# ManualShield.net
KiCad netlist of a schematic drawn in EAGLE
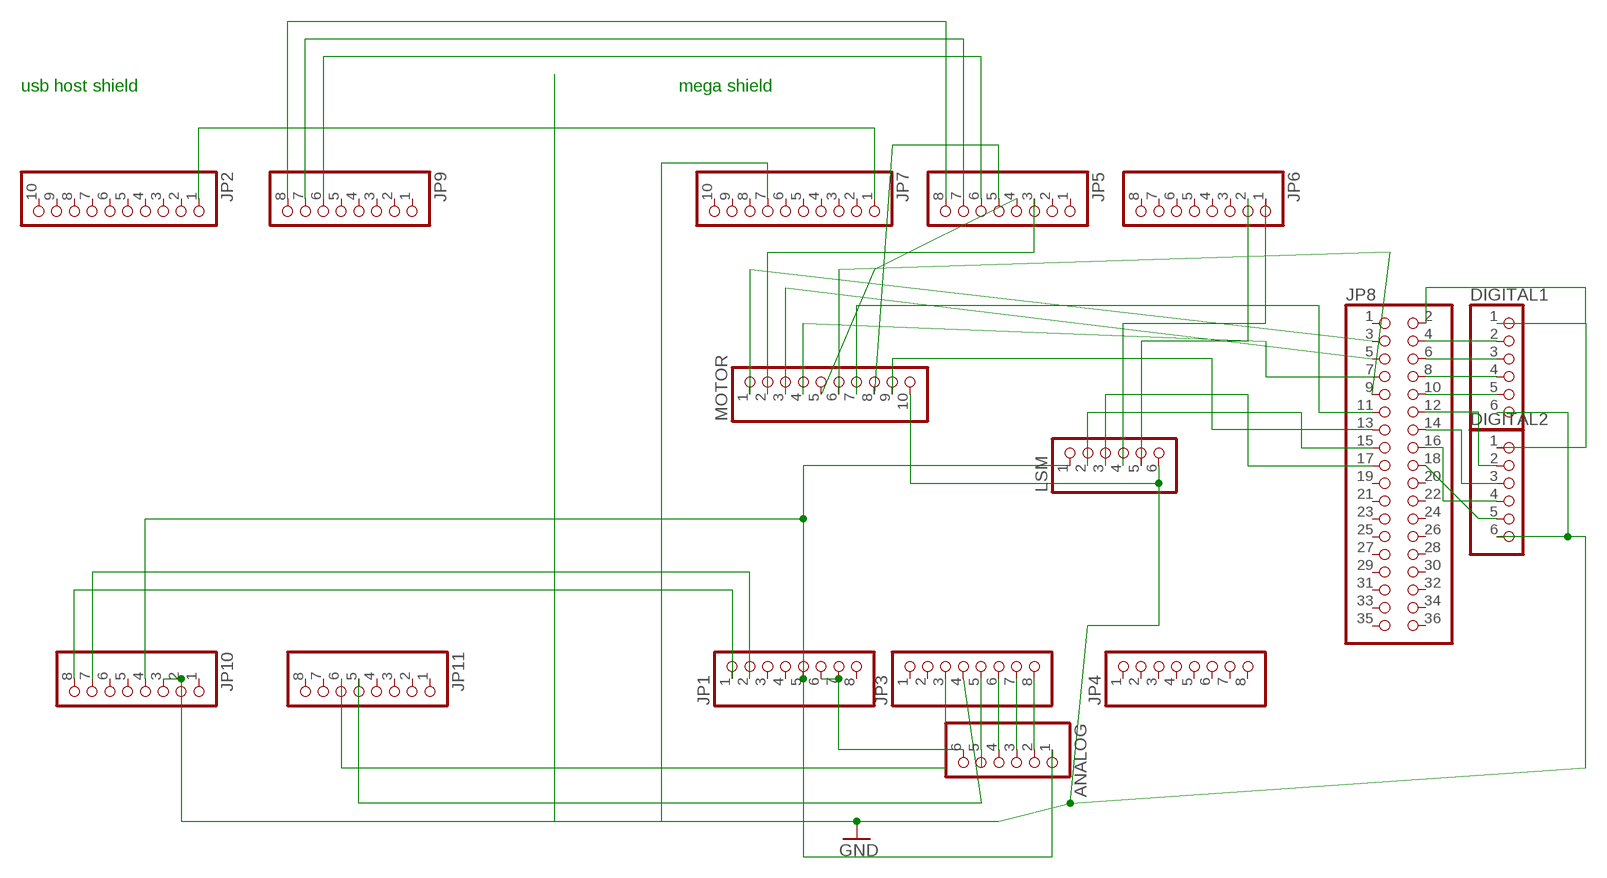
[diagram p0: schematic, sheet 1]

(export (version "E")
  (design (tool "Eeschema 10.0.6"))
  (components
    (comp (ref "ANALOG")
      (value "PINHD-1X6")
      (footprint "eagle-import:1X06")
      (libsource (lib "eagle-import") (part "PINHD-1X6"))
    )
    (comp (ref "DIGITAL1")
      (value "PINHD-1X6")
      (footprint "eagle-import:1X06")
      (libsource (lib "eagle-import") (part "PINHD-1X6"))
    )
    (comp (ref "DIGITAL2")
      (value "PINHD-1X6")
      (footprint "eagle-import:1X06")
      (libsource (lib "eagle-import") (part "PINHD-1X6"))
    )
    (comp (ref "JP1")
      (value "PINHD-1X8")
      (footprint "eagle-import:1X08")
      (libsource (lib "eagle-import") (part "PINHD-1X8"))
    )
    (comp (ref "JP2")
      (value "PINHD-1X10")
      (footprint "eagle-import:1X10")
      (libsource (lib "eagle-import") (part "PINHD-1X10"))
    )
    (comp (ref "JP3")
      (value "PINHD-1X8")
      (footprint "eagle-import:1X08")
      (libsource (lib "eagle-import") (part "PINHD-1X8"))
    )
    (comp (ref "JP4")
      (value "PINHD-1X8")
      (footprint "eagle-import:1X08")
      (libsource (lib "eagle-import") (part "PINHD-1X8"))
    )
    (comp (ref "JP5")
      (value "PINHD-1X8")
      (footprint "eagle-import:1X08")
      (libsource (lib "eagle-import") (part "PINHD-1X8"))
    )
    (comp (ref "JP6")
      (value "PINHD-1X8")
      (footprint "eagle-import:1X08")
      (libsource (lib "eagle-import") (part "PINHD-1X8"))
    )
    (comp (ref "JP7")
      (value "PINHD-1X10")
      (footprint "eagle-import:1X10")
      (libsource (lib "eagle-import") (part "PINHD-1X10"))
    )
    (comp (ref "JP8")
      (value "PINHD-2X18")
      (footprint "eagle-import:2X18")
      (libsource (lib "eagle-import") (part "PINHD-2X18"))
    )
    (comp (ref "JP9")
      (value "PINHD-1X8")
      (footprint "eagle-import:1X08")
      (libsource (lib "eagle-import") (part "PINHD-1X8"))
    )
    (comp (ref "JP10")
      (value "PINHD-1X8")
      (footprint "eagle-import:1X08")
      (libsource (lib "eagle-import") (part "PINHD-1X8"))
    )
    (comp (ref "JP11")
      (value "PINHD-1X8")
      (footprint "eagle-import:1X08")
      (libsource (lib "eagle-import") (part "PINHD-1X8"))
    )
    (comp (ref "LSM")
      (value "PINHD-1X6")
      (footprint "eagle-import:1X06")
      (libsource (lib "eagle-import") (part "PINHD-1X6"))
    )
    (comp (ref "MOTOR")
      (value "PINHD-1X10")
      (footprint "eagle-import:1X10")
      (libsource (lib "eagle-import") (part "pinhead_325_PINHD-1X10"))
    )
  )
  (nets
    (net (code "1") (name "GND") (class "Default")
      (node (ref "DIGITAL1") (pin "6") (pinfunction "6_6") (pintype "passive"))
      (node (ref "DIGITAL2") (pin "6") (pinfunction "6_6") (pintype "passive"))
      (node (ref "JP10") (pin "2") (pinfunction "2_2") (pintype "passive"))
      (node (ref "JP10") (pin "3") (pinfunction "3_3") (pintype "passive"))
      (node (ref "JP7") (pin "7") (pinfunction "7_7") (pintype "passive"))
      (node (ref "LSM") (pin "6") (pinfunction "6_6") (pintype "passive"))
      (node (ref "MOTOR") (pin "10") (pinfunction "10_10") (pintype "passive"))
    )
    (net (code "2") (name "Net-(ANALOG-Pad1)") (class "Default")
      (node (ref "ANALOG") (pin "1") (pinfunction "1_1") (pintype "passive"))
      (node (ref "JP1") (pin "5") (pinfunction "5_5") (pintype "passive"))
      (node (ref "JP10") (pin "4") (pinfunction "4_4") (pintype "passive"))
      (node (ref "LSM") (pin "1") (pinfunction "1_1") (pintype "passive"))
    )
    (net (code "3") (name "Net-(ANALOG-Pad2)") (class "Default")
      (node (ref "ANALOG") (pin "2") (pinfunction "2_2") (pintype "passive"))
      (node (ref "JP3") (pin "8") (pinfunction "8_8") (pintype "passive"))
    )
    (net (code "4") (name "Net-(ANALOG-Pad3)") (class "Default")
      (node (ref "ANALOG") (pin "3") (pinfunction "3_3") (pintype "passive"))
      (node (ref "JP3") (pin "7") (pinfunction "7_7") (pintype "passive"))
    )
    (net (code "5") (name "Net-(ANALOG-Pad4)") (class "Default")
      (node (ref "ANALOG") (pin "4") (pinfunction "4_4") (pintype "passive"))
      (node (ref "JP3") (pin "6") (pinfunction "6_6") (pintype "passive"))
    )
    (net (code "6") (name "Net-(ANALOG-Pad5)") (class "Default")
      (node (ref "ANALOG") (pin "5") (pinfunction "5_5") (pintype "passive"))
      (node (ref "JP3") (pin "5") (pinfunction "5_5") (pintype "passive"))
    )
    (net (code "7") (name "Net-(ANALOG-Pad6)") (class "Default")
      (node (ref "ANALOG") (pin "6") (pinfunction "6_6") (pintype "passive"))
      (node (ref "JP1") (pin "6") (pinfunction "6_6") (pintype "passive"))
      (node (ref "JP1") (pin "7") (pinfunction "7_7") (pintype "passive"))
    )
    (net (code "8") (name "Net-(DIGITAL1-Pad1)") (class "Default")
      (node (ref "DIGITAL1") (pin "1") (pinfunction "1_1") (pintype "passive"))
      (node (ref "DIGITAL2") (pin "1") (pinfunction "1_1") (pintype "passive"))
      (node (ref "JP8") (pin "2") (pinfunction "2_2") (pintype "passive"))
    )
    (net (code "9") (name "Net-(DIGITAL1-Pad2)") (class "Default")
      (node (ref "DIGITAL1") (pin "2") (pinfunction "2_2") (pintype "passive"))
      (node (ref "JP8") (pin "4") (pinfunction "4_4") (pintype "passive"))
    )
    (net (code "10") (name "Net-(DIGITAL1-Pad3)") (class "Default")
      (node (ref "DIGITAL1") (pin "3") (pinfunction "3_3") (pintype "passive"))
      (node (ref "JP8") (pin "6") (pinfunction "6_6") (pintype "passive"))
    )
    (net (code "11") (name "Net-(DIGITAL1-Pad4)") (class "Default")
      (node (ref "DIGITAL1") (pin "4") (pinfunction "4_4") (pintype "passive"))
      (node (ref "JP8") (pin "8") (pinfunction "8_8") (pintype "passive"))
    )
    (net (code "12") (name "Net-(DIGITAL1-Pad5)") (class "Default")
      (node (ref "DIGITAL1") (pin "5") (pinfunction "5_5") (pintype "passive"))
      (node (ref "JP8") (pin "10") (pinfunction "10_10") (pintype "passive"))
    )
    (net (code "13") (name "Net-(DIGITAL2-Pad2)") (class "Default")
      (node (ref "DIGITAL2") (pin "2") (pinfunction "2_2") (pintype "passive"))
      (node (ref "JP8") (pin "12") (pinfunction "12_12") (pintype "passive"))
    )
    (net (code "14") (name "Net-(DIGITAL2-Pad3)") (class "Default")
      (node (ref "DIGITAL2") (pin "3") (pinfunction "3_3") (pintype "passive"))
      (node (ref "JP8") (pin "14") (pinfunction "14_14") (pintype "passive"))
    )
    (net (code "15") (name "Net-(DIGITAL2-Pad4)") (class "Default")
      (node (ref "DIGITAL2") (pin "4") (pinfunction "4_4") (pintype "passive"))
      (node (ref "JP8") (pin "16") (pinfunction "16_16") (pintype "passive"))
    )
    (net (code "16") (name "Net-(DIGITAL2-Pad5)") (class "Default")
      (node (ref "DIGITAL2") (pin "5") (pinfunction "5_5") (pintype "passive"))
      (node (ref "JP8") (pin "18") (pinfunction "18_18") (pintype "passive"))
    )
    (net (code "17") (name "Net-(JP1-Pad1)") (class "Default")
      (node (ref "JP1") (pin "1") (pinfunction "1_1") (pintype "passive"))
      (node (ref "JP10") (pin "8") (pinfunction "8_8") (pintype "passive"))
    )
    (net (code "18") (name "Net-(JP1-Pad2)") (class "Default")
      (node (ref "JP1") (pin "2") (pinfunction "2_2") (pintype "passive"))
      (node (ref "JP10") (pin "7") (pinfunction "7_7") (pintype "passive"))
    )
    (net (code "19") (name "Net-(JP2-Pad1)") (class "Default")
      (node (ref "JP2") (pin "1") (pinfunction "1_1") (pintype "passive"))
      (node (ref "JP7") (pin "1") (pinfunction "1_1") (pintype "passive"))
    )
    (net (code "20") (name "Net-(JP5-Pad3)") (class "Default")
      (node (ref "JP5") (pin "3") (pinfunction "3_3") (pintype "passive"))
      (node (ref "MOTOR") (pin "2") (pinfunction "2_2") (pintype "passive"))
    )
    (net (code "21") (name "Net-(JP5-Pad4)") (class "Default")
      (node (ref "JP5") (pin "4") (pinfunction "4_4") (pintype "passive"))
      (node (ref "MOTOR") (pin "5") (pinfunction "5_5") (pintype "passive"))
    )
    (net (code "22") (name "Net-(JP5-Pad5)") (class "Default")
      (node (ref "JP5") (pin "5") (pinfunction "5_5") (pintype "passive"))
      (node (ref "MOTOR") (pin "8") (pinfunction "8_8") (pintype "passive"))
    )
    (net (code "23") (name "Net-(JP5-Pad6)") (class "Default")
      (node (ref "JP5") (pin "6") (pinfunction "6_6") (pintype "passive"))
      (node (ref "JP9") (pin "6") (pinfunction "6_6") (pintype "passive"))
    )
    (net (code "24") (name "Net-(JP5-Pad7)") (class "Default")
      (node (ref "JP5") (pin "7") (pinfunction "7_7") (pintype "passive"))
      (node (ref "JP9") (pin "7") (pinfunction "7_7") (pintype "passive"))
    )
    (net (code "25") (name "Net-(JP5-Pad8)") (class "Default")
      (node (ref "JP5") (pin "8") (pinfunction "8_8") (pintype "passive"))
      (node (ref "JP9") (pin "8") (pinfunction "8_8") (pintype "passive"))
    )
    (net (code "26") (name "Net-(JP6-Pad1)") (class "Default")
      (node (ref "JP6") (pin "1") (pinfunction "1_1") (pintype "passive"))
      (node (ref "LSM") (pin "4") (pinfunction "4_4") (pintype "passive"))
    )
    (net (code "27") (name "Net-(JP6-Pad2)") (class "Default")
      (node (ref "JP6") (pin "2") (pinfunction "2_2") (pintype "passive"))
      (node (ref "LSM") (pin "5") (pinfunction "5_5") (pintype "passive"))
    )
    (net (code "28") (name "Net-(JP8-Pad3)") (class "Default")
      (node (ref "JP8") (pin "3") (pinfunction "3_3") (pintype "passive"))
      (node (ref "MOTOR") (pin "1") (pinfunction "1_1") (pintype "passive"))
    )
    (net (code "29") (name "Net-(JP8-Pad5)") (class "Default")
      (node (ref "JP8") (pin "5") (pinfunction "5_5") (pintype "passive"))
      (node (ref "MOTOR") (pin "3") (pinfunction "3_3") (pintype "passive"))
    )
    (net (code "30") (name "Net-(JP8-Pad7)") (class "Default")
      (node (ref "JP8") (pin "7") (pinfunction "7_7") (pintype "passive"))
      (node (ref "MOTOR") (pin "4") (pinfunction "4_4") (pintype "passive"))
    )
    (net (code "31") (name "Net-(JP8-Pad9)") (class "Default")
      (node (ref "JP8") (pin "9") (pinfunction "9_9") (pintype "passive"))
      (node (ref "MOTOR") (pin "6") (pinfunction "6_6") (pintype "passive"))
    )
    (net (code "32") (name "Net-(JP8-Pad11)") (class "Default")
      (node (ref "JP8") (pin "11") (pinfunction "11_11") (pintype "passive"))
      (node (ref "MOTOR") (pin "7") (pinfunction "7_7") (pintype "passive"))
    )
    (net (code "33") (name "Net-(JP8-Pad13)") (class "Default")
      (node (ref "JP8") (pin "13") (pinfunction "13_13") (pintype "passive"))
      (node (ref "MOTOR") (pin "9") (pinfunction "9_9") (pintype "passive"))
    )
    (net (code "34") (name "Net-(JP8-Pad15)") (class "Default")
      (node (ref "JP8") (pin "15") (pinfunction "15_15") (pintype "passive"))
      (node (ref "LSM") (pin "2") (pinfunction "2_2") (pintype "passive"))
    )
    (net (code "35") (name "Net-(JP8-Pad17)") (class "Default")
      (node (ref "JP8") (pin "17") (pinfunction "17_17") (pintype "passive"))
      (node (ref "LSM") (pin "3") (pinfunction "3_3") (pintype "passive"))
    )
    (net (code "36") (name "Net-(JP11-Pad5)") (class "Default")
      (node (ref "JP11") (pin "5") (pinfunction "5_5") (pintype "passive"))
      (node (ref "JP3") (pin "4") (pinfunction "4_4") (pintype "passive"))
    )
    (net (code "37") (name "Net-(JP11-Pad6)") (class "Default")
      (node (ref "JP11") (pin "6") (pinfunction "6_6") (pintype "passive"))
      (node (ref "JP3") (pin "3") (pinfunction "3_3") (pintype "passive"))
    )
    (net (code "38") (name "unconnected-(JP1-Pad3)") (class "Default")
      (node (ref "JP1") (pin "3") (pinfunction "3_3") (pintype "passive"))
    )
    (net (code "39") (name "unconnected-(JP1-Pad4)") (class "Default")
      (node (ref "JP1") (pin "4") (pinfunction "4_4") (pintype "passive"))
    )
    (net (code "40") (name "unconnected-(JP1-Pad8)") (class "Default")
      (node (ref "JP1") (pin "8") (pinfunction "8_8") (pintype "passive"))
    )
    (net (code "41") (name "unconnected-(JP2-Pad2)") (class "Default")
      (node (ref "JP2") (pin "2") (pinfunction "2_2") (pintype "passive"))
    )
    (net (code "42") (name "unconnected-(JP2-Pad3)") (class "Default")
      (node (ref "JP2") (pin "3") (pinfunction "3_3") (pintype "passive"))
    )
    (net (code "43") (name "unconnected-(JP2-Pad4)") (class "Default")
      (node (ref "JP2") (pin "4") (pinfunction "4_4") (pintype "passive"))
    )
    (net (code "44") (name "unconnected-(JP2-Pad5)") (class "Default")
      (node (ref "JP2") (pin "5") (pinfunction "5_5") (pintype "passive"))
    )
    (net (code "45") (name "unconnected-(JP2-Pad6)") (class "Default")
      (node (ref "JP2") (pin "6") (pinfunction "6_6") (pintype "passive"))
    )
    (net (code "46") (name "unconnected-(JP2-Pad7)") (class "Default")
      (node (ref "JP2") (pin "7") (pinfunction "7_7") (pintype "passive"))
    )
    (net (code "47") (name "unconnected-(JP2-Pad8)") (class "Default")
      (node (ref "JP2") (pin "8") (pinfunction "8_8") (pintype "passive"))
    )
    (net (code "48") (name "unconnected-(JP2-Pad9)") (class "Default")
      (node (ref "JP2") (pin "9") (pinfunction "9_9") (pintype "passive"))
    )
    (net (code "49") (name "unconnected-(JP2-Pad10)") (class "Default")
      (node (ref "JP2") (pin "10") (pinfunction "10_10") (pintype "passive"))
    )
    (net (code "50") (name "unconnected-(JP3-Pad1)") (class "Default")
      (node (ref "JP3") (pin "1") (pinfunction "1_1") (pintype "passive"))
    )
    (net (code "51") (name "unconnected-(JP3-Pad2)") (class "Default")
      (node (ref "JP3") (pin "2") (pinfunction "2_2") (pintype "passive"))
    )
    (net (code "52") (name "unconnected-(JP4-Pad1)") (class "Default")
      (node (ref "JP4") (pin "1") (pinfunction "1_1") (pintype "passive"))
    )
    (net (code "53") (name "unconnected-(JP4-Pad2)") (class "Default")
      (node (ref "JP4") (pin "2") (pinfunction "2_2") (pintype "passive"))
    )
    (net (code "54") (name "unconnected-(JP4-Pad3)") (class "Default")
      (node (ref "JP4") (pin "3") (pinfunction "3_3") (pintype "passive"))
    )
    (net (code "55") (name "unconnected-(JP4-Pad4)") (class "Default")
      (node (ref "JP4") (pin "4") (pinfunction "4_4") (pintype "passive"))
    )
    (net (code "56") (name "unconnected-(JP4-Pad5)") (class "Default")
      (node (ref "JP4") (pin "5") (pinfunction "5_5") (pintype "passive"))
    )
    (net (code "57") (name "unconnected-(JP4-Pad6)") (class "Default")
      (node (ref "JP4") (pin "6") (pinfunction "6_6") (pintype "passive"))
    )
    (net (code "58") (name "unconnected-(JP4-Pad7)") (class "Default")
      (node (ref "JP4") (pin "7") (pinfunction "7_7") (pintype "passive"))
    )
    (net (code "59") (name "unconnected-(JP4-Pad8)") (class "Default")
      (node (ref "JP4") (pin "8") (pinfunction "8_8") (pintype "passive"))
    )
    (net (code "60") (name "unconnected-(JP5-Pad1)") (class "Default")
      (node (ref "JP5") (pin "1") (pinfunction "1_1") (pintype "passive"))
    )
    (net (code "61") (name "unconnected-(JP5-Pad2)") (class "Default")
      (node (ref "JP5") (pin "2") (pinfunction "2_2") (pintype "passive"))
    )
    (net (code "62") (name "unconnected-(JP6-Pad3)") (class "Default")
      (node (ref "JP6") (pin "3") (pinfunction "3_3") (pintype "passive"))
    )
    (net (code "63") (name "unconnected-(JP6-Pad4)") (class "Default")
      (node (ref "JP6") (pin "4") (pinfunction "4_4") (pintype "passive"))
    )
    (net (code "64") (name "unconnected-(JP6-Pad5)") (class "Default")
      (node (ref "JP6") (pin "5") (pinfunction "5_5") (pintype "passive"))
    )
    (net (code "65") (name "unconnected-(JP6-Pad6)") (class "Default")
      (node (ref "JP6") (pin "6") (pinfunction "6_6") (pintype "passive"))
    )
    (net (code "66") (name "unconnected-(JP6-Pad7)") (class "Default")
      (node (ref "JP6") (pin "7") (pinfunction "7_7") (pintype "passive"))
    )
    (net (code "67") (name "unconnected-(JP6-Pad8)") (class "Default")
      (node (ref "JP6") (pin "8") (pinfunction "8_8") (pintype "passive"))
    )
    (net (code "68") (name "unconnected-(JP7-Pad2)") (class "Default")
      (node (ref "JP7") (pin "2") (pinfunction "2_2") (pintype "passive"))
    )
    (net (code "69") (name "unconnected-(JP7-Pad3)") (class "Default")
      (node (ref "JP7") (pin "3") (pinfunction "3_3") (pintype "passive"))
    )
    (net (code "70") (name "unconnected-(JP7-Pad4)") (class "Default")
      (node (ref "JP7") (pin "4") (pinfunction "4_4") (pintype "passive"))
    )
    (net (code "71") (name "unconnected-(JP7-Pad5)") (class "Default")
      (node (ref "JP7") (pin "5") (pinfunction "5_5") (pintype "passive"))
    )
    (net (code "72") (name "unconnected-(JP7-Pad6)") (class "Default")
      (node (ref "JP7") (pin "6") (pinfunction "6_6") (pintype "passive"))
    )
    (net (code "73") (name "unconnected-(JP7-Pad8)") (class "Default")
      (node (ref "JP7") (pin "8") (pinfunction "8_8") (pintype "passive"))
    )
    (net (code "74") (name "unconnected-(JP7-Pad9)") (class "Default")
      (node (ref "JP7") (pin "9") (pinfunction "9_9") (pintype "passive"))
    )
    (net (code "75") (name "unconnected-(JP7-Pad10)") (class "Default")
      (node (ref "JP7") (pin "10") (pinfunction "10_10") (pintype "passive"))
    )
    (net (code "76") (name "unconnected-(JP8-Pad1)") (class "Default")
      (node (ref "JP8") (pin "1") (pinfunction "1_1") (pintype "passive"))
    )
    (net (code "77") (name "unconnected-(JP8-Pad19)") (class "Default")
      (node (ref "JP8") (pin "19") (pinfunction "19_19") (pintype "passive"))
    )
    (net (code "78") (name "unconnected-(JP8-Pad20)") (class "Default")
      (node (ref "JP8") (pin "20") (pinfunction "20_20") (pintype "passive"))
    )
    (net (code "79") (name "unconnected-(JP8-Pad21)") (class "Default")
      (node (ref "JP8") (pin "21") (pinfunction "21_21") (pintype "passive"))
    )
    (net (code "80") (name "unconnected-(JP8-Pad22)") (class "Default")
      (node (ref "JP8") (pin "22") (pinfunction "22_22") (pintype "passive"))
    )
    (net (code "81") (name "unconnected-(JP8-Pad23)") (class "Default")
      (node (ref "JP8") (pin "23") (pinfunction "23_23") (pintype "passive"))
    )
    (net (code "82") (name "unconnected-(JP8-Pad24)") (class "Default")
      (node (ref "JP8") (pin "24") (pinfunction "24_24") (pintype "passive"))
    )
    (net (code "83") (name "unconnected-(JP8-Pad25)") (class "Default")
      (node (ref "JP8") (pin "25") (pinfunction "25_25") (pintype "passive"))
    )
    (net (code "84") (name "unconnected-(JP8-Pad26)") (class "Default")
      (node (ref "JP8") (pin "26") (pinfunction "26_26") (pintype "passive"))
    )
    (net (code "85") (name "unconnected-(JP8-Pad27)") (class "Default")
      (node (ref "JP8") (pin "27") (pinfunction "27_27") (pintype "passive"))
    )
    (net (code "86") (name "unconnected-(JP8-Pad28)") (class "Default")
      (node (ref "JP8") (pin "28") (pinfunction "28_28") (pintype "passive"))
    )
    (net (code "87") (name "unconnected-(JP8-Pad29)") (class "Default")
      (node (ref "JP8") (pin "29") (pinfunction "29_29") (pintype "passive"))
    )
    (net (code "88") (name "unconnected-(JP8-Pad30)") (class "Default")
      (node (ref "JP8") (pin "30") (pinfunction "30_30") (pintype "passive"))
    )
    (net (code "89") (name "unconnected-(JP8-Pad31)") (class "Default")
      (node (ref "JP8") (pin "31") (pinfunction "31_31") (pintype "passive"))
    )
    (net (code "90") (name "unconnected-(JP8-Pad32)") (class "Default")
      (node (ref "JP8") (pin "32") (pinfunction "32_32") (pintype "passive"))
    )
    (net (code "91") (name "unconnected-(JP8-Pad33)") (class "Default")
      (node (ref "JP8") (pin "33") (pinfunction "33_33") (pintype "passive"))
    )
    (net (code "92") (name "unconnected-(JP8-Pad34)") (class "Default")
      (node (ref "JP8") (pin "34") (pinfunction "34_34") (pintype "passive"))
    )
    (net (code "93") (name "unconnected-(JP8-Pad35)") (class "Default")
      (node (ref "JP8") (pin "35") (pinfunction "35_35") (pintype "passive"))
    )
    (net (code "94") (name "unconnected-(JP8-Pad36)") (class "Default")
      (node (ref "JP8") (pin "36") (pinfunction "36_36") (pintype "passive"))
    )
    (net (code "95") (name "unconnected-(JP9-Pad1)") (class "Default")
      (node (ref "JP9") (pin "1") (pinfunction "1_1") (pintype "passive"))
    )
    (net (code "96") (name "unconnected-(JP9-Pad2)") (class "Default")
      (node (ref "JP9") (pin "2") (pinfunction "2_2") (pintype "passive"))
    )
    (net (code "97") (name "unconnected-(JP9-Pad3)") (class "Default")
      (node (ref "JP9") (pin "3") (pinfunction "3_3") (pintype "passive"))
    )
    (net (code "98") (name "unconnected-(JP9-Pad4)") (class "Default")
      (node (ref "JP9") (pin "4") (pinfunction "4_4") (pintype "passive"))
    )
    (net (code "99") (name "unconnected-(JP9-Pad5)") (class "Default")
      (node (ref "JP9") (pin "5") (pinfunction "5_5") (pintype "passive"))
    )
    (net (code "100") (name "unconnected-(JP10-Pad1)") (class "Default")
      (node (ref "JP10") (pin "1") (pinfunction "1_1") (pintype "passive"))
    )
    (net (code "101") (name "unconnected-(JP10-Pad5)") (class "Default")
      (node (ref "JP10") (pin "5") (pinfunction "5_5") (pintype "passive"))
    )
    (net (code "102") (name "unconnected-(JP10-Pad6)") (class "Default")
      (node (ref "JP10") (pin "6") (pinfunction "6_6") (pintype "passive"))
    )
    (net (code "103") (name "unconnected-(JP11-Pad1)") (class "Default")
      (node (ref "JP11") (pin "1") (pinfunction "1_1") (pintype "passive"))
    )
    (net (code "104") (name "unconnected-(JP11-Pad2)") (class "Default")
      (node (ref "JP11") (pin "2") (pinfunction "2_2") (pintype "passive"))
    )
    (net (code "105") (name "unconnected-(JP11-Pad3)") (class "Default")
      (node (ref "JP11") (pin "3") (pinfunction "3_3") (pintype "passive"))
    )
    (net (code "106") (name "unconnected-(JP11-Pad4)") (class "Default")
      (node (ref "JP11") (pin "4") (pinfunction "4_4") (pintype "passive"))
    )
    (net (code "107") (name "unconnected-(JP11-Pad7)") (class "Default")
      (node (ref "JP11") (pin "7") (pinfunction "7_7") (pintype "passive"))
    )
    (net (code "108") (name "unconnected-(JP11-Pad8)") (class "Default")
      (node (ref "JP11") (pin "8") (pinfunction "8_8") (pintype "passive"))
    )
  )
)
